# pulse_gen.net
KiCad netlist of a schematic drawn in Altium Designer
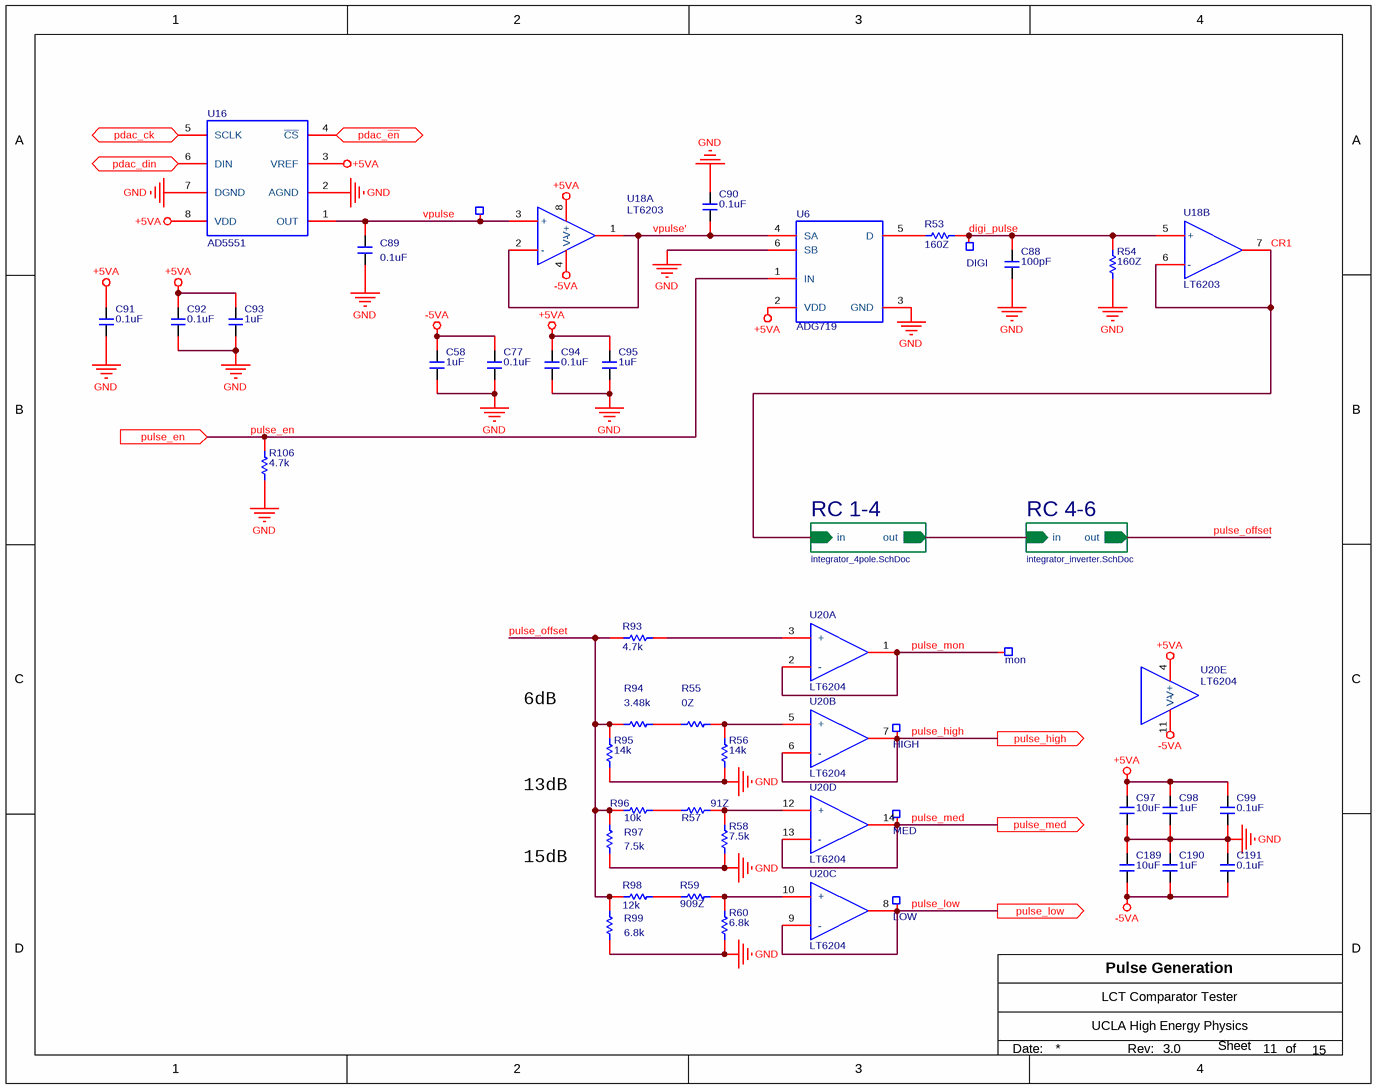
[diagram p0: pulse_gen.SchDoc]

(export (version "E")
  (design (tool "Eeschema 10.0.6"))
  (components
    (comp (ref "C58")
      (value "1uF")
      (footprint "C0603")
      (description "CAP-CER, 2, 1.0uF, 10%, 25V, 0603")
      (fields
        (field (name "MANUFACTURER") "Murata Electronics North America")
        (field (name "MANUFACTURER PART NUMBER") "GRM188R61E105KA12D")
      )
      (libsource (lib "stdlib") (part "Murata/GRM188R61E105KA12D"))
    )
    (comp (ref "C77")
      (value "0.1uF")
      (footprint "C0603")
      (description "CAP-CER, 2, 0.1uF, 10%, 50V, 0603, X7R")
      (fields
        (field (name "MANUFACTURER") "AVX Corporation")
        (field (name "MANUFACTURER PART NUMBER") "06035C104KAT2A")
      )
      (libsource (lib "stdlib") (part "CAP/06035C104KAT2A"))
    )
    (comp (ref "C88")
      (value "100pF")
      (footprint "C0603")
      (description "CAP-CER, 0, 100pF, 10%, 50V, 0603")
      (fields
        (field (name "MANUFACTURER") "AVX Corporation")
        (field (name "MANUFACTURER PART NUMBER") "06035A101KAT2A")
      )
      (libsource (lib "stdlib") (part "AVX/06035A101KAT2A"))
    )
    (comp (ref "C89")
      (value "0.1uF")
      (footprint "C0603")
      (description "CAP-CER, 2, 0.1uF, 10%, 50V, 0603, X7R")
      (fields
        (field (name "MANUFACTURER") "AVX Corporation")
        (field (name "MANUFACTURER PART NUMBER") "06035C104KAT2A")
      )
      (libsource (lib "stdlib") (part "CAP/06035C104KAT2A"))
    )
    (comp (ref "C90")
      (value "0.1uF")
      (footprint "C0603")
      (description "CAP-CER, 2, 0.1uF, 10%, 50V, 0603, X7R")
      (fields
        (field (name "MANUFACTURER") "AVX Corporation")
        (field (name "MANUFACTURER PART NUMBER") "06035C104KAT2A")
      )
      (libsource (lib "stdlib") (part "CAP/06035C104KAT2A"))
    )
    (comp (ref "C91")
      (value "0.1uF")
      (footprint "C0603")
      (description "CAP-CER, 2, 0.1uF, 10%, 50V, 0603, X7R")
      (fields
        (field (name "MANUFACTURER") "AVX Corporation")
        (field (name "MANUFACTURER PART NUMBER") "06035C104KAT2A")
      )
      (libsource (lib "stdlib") (part "CAP/06035C104KAT2A"))
    )
    (comp (ref "C92")
      (value "0.1uF")
      (footprint "C0603")
      (description "CAP-CER, 2, 0.1uF, 10%, 50V, 0603, X7R")
      (fields
        (field (name "MANUFACTURER") "AVX Corporation")
        (field (name "MANUFACTURER PART NUMBER") "06035C104KAT2A")
      )
      (libsource (lib "stdlib") (part "CAP/06035C104KAT2A"))
    )
    (comp (ref "C93")
      (value "1uF")
      (footprint "C0603")
      (description "CAP-CER, 2, 1.0uF, 10%, 25V, 0603")
      (fields
        (field (name "MANUFACTURER") "Murata Electronics North America")
        (field (name "MANUFACTURER PART NUMBER") "GRM188R61E105KA12D")
      )
      (libsource (lib "stdlib") (part "Murata/GRM188R61E105KA12D"))
    )
    (comp (ref "C94")
      (value "0.1uF")
      (footprint "C0603")
      (description "CAP-CER, 2, 0.1uF, 10%, 50V, 0603, X7R")
      (fields
        (field (name "MANUFACTURER") "AVX Corporation")
        (field (name "MANUFACTURER PART NUMBER") "06035C104KAT2A")
      )
      (libsource (lib "stdlib") (part "CAP/06035C104KAT2A"))
    )
    (comp (ref "C95")
      (value "1uF")
      (footprint "C0603")
      (description "CAP-CER, 2, 1.0uF, 10%, 25V, 0603")
      (fields
        (field (name "MANUFACTURER") "Murata Electronics North America")
        (field (name "MANUFACTURER PART NUMBER") "GRM188R61E105KA12D")
      )
      (libsource (lib "stdlib") (part "Murata/GRM188R61E105KA12D"))
    )
    (comp (ref "C97")
      (value "10uF")
      (footprint "c1206")
      (description "CAP-CER, 2, 10uF, 10%, 35V, 1206")
      (fields
        (field (name "MANUFACTURER") "Taiyo Yuden")
        (field (name "MANUFACTURER PART NUMBER") "GMK316F106ZL-T")
      )
      (libsource (lib "stdlib") (part "CAP/GMK316F106ZL-T"))
    )
    (comp (ref "C98")
      (value "1uF")
      (footprint "C0603")
      (description "CAP-CER, 2, 1.0uF, 10%, 25V, 0603")
      (fields
        (field (name "MANUFACTURER") "Murata Electronics North America")
        (field (name "MANUFACTURER PART NUMBER") "GRM188R61E105KA12D")
      )
      (libsource (lib "stdlib") (part "Murata/GRM188R61E105KA12D"))
    )
    (comp (ref "C99")
      (value "0.1uF")
      (footprint "C0603")
      (description "CAP-CER, 2, 0.1uF, 10%, 50V, 0603, X7R")
      (fields
        (field (name "MANUFACTURER") "AVX Corporation")
        (field (name "MANUFACTURER PART NUMBER") "06035C104KAT2A")
      )
      (libsource (lib "stdlib") (part "CAP/06035C104KAT2A"))
    )
    (comp (ref "C189")
      (value "10uF")
      (footprint "c1206")
      (description "CAP-CER, 2, 10uF, 10%, 35V, 1206")
      (fields
        (field (name "MANUFACTURER") "Taiyo Yuden")
        (field (name "MANUFACTURER PART NUMBER") "GMK316F106ZL-T")
      )
      (libsource (lib "stdlib") (part "CAP/GMK316F106ZL-T"))
    )
    (comp (ref "C190")
      (value "1uF")
      (footprint "C0603")
      (description "CAP-CER, 2, 1.0uF, 10%, 25V, 0603")
      (fields
        (field (name "MANUFACTURER") "Murata Electronics North America")
        (field (name "MANUFACTURER PART NUMBER") "GRM188R61E105KA12D")
      )
      (libsource (lib "stdlib") (part "Murata/GRM188R61E105KA12D"))
    )
    (comp (ref "C191")
      (value "0.1uF")
      (footprint "C0603")
      (description "CAP-CER, 2, 0.1uF, 10%, 50V, 0603, X7R")
      (fields
        (field (name "MANUFACTURER") "AVX Corporation")
        (field (name "MANUFACTURER PART NUMBER") "06035C104KAT2A")
      )
      (libsource (lib "stdlib") (part "CAP/06035C104KAT2A"))
    )
    (comp (ref "mon")
      (value "TP_SMALL")
      (footprint "TP_SMALL")
      (description "Test Point, Generic, 50MIL")
      (libsource (lib "stdlib") (part "TP_SMALL"))
    )
    (comp (ref "R53")
      (value "160Z")
      (footprint "R0603")
      (description "RES0, SMD,  160Z, 1.0%, 1/10W, 0603")
      (fields
        (field (name "MANUFACTURER") "Vishay Dale")
        (field (name "MANUFACTURER PART NUMBER") "CRCW0603160RFKEA")
      )
      (libsource (lib "stdlib") (part "CRCW0603160RFKEA"))
    )
    (comp (ref "R54")
      (value "160Z")
      (footprint "R0603")
      (description "RES0, SMD,  160Z, 1.0%, 1/10W, 0603")
      (fields
        (field (name "MANUFACTURER") "Vishay Dale")
        (field (name "MANUFACTURER PART NUMBER") "CRCW0603160RFKEA")
      )
      (libsource (lib "stdlib") (part "CRCW0603160RFKEA"))
    )
    (comp (ref "R55")
      (value "0Z")
      (footprint "R0805")
      (description "RES0, SMD, 0.00Z, 0805")
      (fields
        (field (name "MANUFACTURER") "Vishay Dale")
        (field (name "MANUFACTURER PART NUMBER") "CRCW08050000Z0EA")
      )
      (libsource (lib "stdlib") (part "CRCW08050000Z0EA"))
    )
    (comp (ref "R56")
      (value "14k")
      (footprint "R0805")
      (description "RES1, SMD, 14.0k, 1.0%, 1/8W, 0805")
      (fields
        (field (name "MANUFACTURER") "Yageo")
        (field (name "MANUFACTURER PART NUMBER") "RC0805FR-0714KL")
      )
      (libsource (lib "stdlib") (part "RC0805FR-0714KL"))
    )
    (comp (ref "R57")
      (value "91Z")
      (footprint "R0805")
      (description "RES0, SMD, 91Z, 1.0%, 1/8W, 0805")
      (fields
        (field (name "MANUFACTURER") "Panasonic Electronic Components")
        (field (name "MANUFACTURER PART NUMBER") "ERJ-6ENF91R0V")
      )
      (libsource (lib "stdlib") (part "ERJ-6ENF91R0V"))
    )
    (comp (ref "R58")
      (value "7.5k")
      (footprint "R0805")
      (description "RES1, SMD, 7.5k, 1.0%, 1/8W, 0805")
      (fields
        (field (name "MANUFACTURER") "Yageo")
        (field (name "MANUFACTURER PART NUMBER") "RC0805FR-077K5L")
      )
      (libsource (lib "stdlib") (part "RC0805FR-077K5L"))
    )
    (comp (ref "R59")
      (value "909Z")
      (footprint "R0805")
      (description "RES0, SMD, 6.8k, 1.0%, 1/8W, 0805")
      (fields
        (field (name "MANUFACTURER") "Yageo")
        (field (name "MANUFACTURER PART NUMBER") "RC0805FR-07909RL")
      )
      (libsource (lib "stdlib") (part "RC0805FR-07909RL"))
    )
    (comp (ref "R60")
      (value "6.8k")
      (footprint "R0805")
      (description "RES1, SMD, 6.8k, 1.0%, 1/8W, 0805")
      (fields
        (field (name "MANUFACTURER") "Yageo")
        (field (name "MANUFACTURER PART NUMBER") "RC0805FR-076K8L")
      )
      (libsource (lib "stdlib") (part "RC0805FR-076K8L"))
    )
    (comp (ref "R93")
      (value "4.7k")
      (footprint "R0805")
      (description "RES1, SMD, 4.70k, 1.0%, 1/10W, 0805")
      (fields
        (field (name "MANUFACTURER") "Vishay Dale")
        (field (name "MANUFACTURER PART NUMBER") "CRCW08054K70FKEA")
      )
      (libsource (lib "stdlib") (part "CRCW08054K70FKEA"))
    )
    (comp (ref "R94")
      (value "3.48k")
      (footprint "R0805")
      (description "RES1, SMD, 3.48k, 1.0%, 1/10W, 0805")
      (fields
        (field (name "MANUFACTURER") "Yageo")
        (field (name "MANUFACTURER PART NUMBER") "RC0805FR-073K48L")
      )
      (libsource (lib "stdlib") (part "RC0805FR-073K48L"))
    )
    (comp (ref "R95")
      (value "14k")
      (footprint "R0805")
      (description "RES1, SMD, 14.0k, 1.0%, 1/8W, 0805")
      (fields
        (field (name "MANUFACTURER") "Yageo")
        (field (name "MANUFACTURER PART NUMBER") "RC0805FR-0714KL")
      )
      (libsource (lib "stdlib") (part "RC0805FR-0714KL"))
    )
    (comp (ref "R96")
      (value "10k")
      (footprint "R0805")
      (description "RES1, SMD, 10.0k, 1.0%, 1/8W, 0805")
      (fields
        (field (name "MANUFACTURER") "Yageo")
        (field (name "MANUFACTURER PART NUMBER") "RC0805FR-0710KL")
      )
      (libsource (lib "stdlib") (part "RC0805FR-0710KL"))
    )
    (comp (ref "R97")
      (value "7.5k")
      (footprint "R0805")
      (description "RES1, SMD, 7.5k, 1.0%, 1/8W, 0805")
      (fields
        (field (name "MANUFACTURER") "Yageo")
        (field (name "MANUFACTURER PART NUMBER") "RC0805FR-077K5L")
      )
      (libsource (lib "stdlib") (part "RC0805FR-077K5L"))
    )
    (comp (ref "R98")
      (value "12k")
      (footprint "R0805")
      (description "RES1, SMD, 12.0k, 1.0%, 1/8W, 0805")
      (fields
        (field (name "MANUFACTURER") "Yageo")
        (field (name "MANUFACTURER PART NUMBER") "RC0805FR-0712KL")
      )
      (libsource (lib "stdlib") (part "RC0805FR-0712KL"))
    )
    (comp (ref "R99")
      (value "6.8k")
      (footprint "R0805")
      (description "RES1, SMD, 6.8k, 1.0%, 1/8W, 0805")
      (fields
        (field (name "MANUFACTURER") "Yageo")
        (field (name "MANUFACTURER PART NUMBER") "RC0805FR-076K8L")
      )
      (libsource (lib "stdlib") (part "RC0805FR-076K8L"))
    )
    (comp (ref "R106")
      (value "4.7k")
      (footprint "R0603")
      (description "RES1, SMD, 4.70k, 1.0%, 1/10W, 0603")
      (fields
        (field (name "MANUFACTURER") "Vishay Dale")
        (field (name "MANUFACTURER PART NUMBER") "CRCW06034K70FKEA")
      )
      (libsource (lib "stdlib") (part "CRCW06034K70FKEA"))
    )
    (comp (ref "TP27")
      (value "PDAC")
      (footprint "TP_MICRO")
      (description "Test Point, Round, Small")
      (libsource (lib "stdlib") (part "TP_MICRO"))
    )
    (comp (ref "TP28")
      (value "DIGI")
      (footprint "TP_MICRO")
      (description "Test Point, Round, Small")
      (libsource (lib "") (part "TP_MICRO_1"))
    )
    (comp (ref "TP29")
      (value "HIGH")
      (footprint "TP_MICRO")
      (description "Test Point, Round, Small")
      (libsource (lib "stdlib") (part "TP_MICRO"))
    )
    (comp (ref "TP30")
      (value "MED")
      (footprint "TP_MICRO")
      (description "Test Point, Round, Small")
      (libsource (lib "stdlib") (part "TP_MICRO"))
    )
    (comp (ref "TP31")
      (value "LOW")
      (footprint "TP_MICRO")
      (description "Test Point, Round, Small")
      (libsource (lib "stdlib") (part "TP_MICRO"))
    )
    (comp (ref "U6")
      (value "ADG719")
      (footprint "SOT23-6")
      (description "SWITCH, SPDT, 2:1, 4 Ohm")
      (fields
        (field (name "MANUFACTURER") "Analog Devices Inc.")
        (field (name "MANUFACTURER PART NUMBER") "ADG719BRTZ-500RL7")
      )
      (libsource (lib "stdlib") (part "ADG719 SOT23-6"))
    )
    (comp (ref "U16")
      (value "AD5551")
      (footprint "SOIC-8")
      (description "DAC, 14-BIT, 1MSPS")
      (fields
        (field (name "MANUFACTURER") "Analog Devices Inc.")
        (field (name "MANUFACTURER PART NUMBER") "AD5551BRZ")
      )
      (libsource (lib "stdlib") (part "AD/AD5551 SOIC-8"))
    )
    (comp (ref "U18")
      (value "LT6203")
      (footprint "SOIC-8")
      (description "OPA, 100MHz, Dual, RRIO, Single-supply, Unity Stable")
      (libsource (lib "stdlib") (part "LT6203 SOIC-8"))
    )
    (comp (ref "U20")
      (value "LT6204")
      (footprint "SOIC-14")
      (description "OPA, 100MHz, Quad, RRIO, Unity Stable")
      (libsource (lib "stdlib") (part "LT6204 SOIC-14"))
    )
  )
  (nets
    (net (code "1") (name "+5VA") (class "Default")
      (node (ref "C91") (pin "2") (pinfunction "2_2") (pintype "passive"))
      (node (ref "C92") (pin "2") (pinfunction "2_2") (pintype "passive"))
      (node (ref "C93") (pin "2") (pinfunction "2_2") (pintype "passive"))
      (node (ref "C94") (pin "2") (pinfunction "2_2") (pintype "passive"))
      (node (ref "C95") (pin "2") (pinfunction "2_2") (pintype "passive"))
      (node (ref "C97") (pin "1") (pinfunction "5_1") (pintype "passive"))
      (node (ref "C98") (pin "2") (pinfunction "2_2") (pintype "passive"))
      (node (ref "C99") (pin "2") (pinfunction "2_2") (pintype "passive"))
      (node (ref "U16") (pin "3") (pinfunction "VREF_3") (pintype "passive"))
      (node (ref "U16") (pin "8") (pinfunction "VDD_8") (pintype "passive"))
      (node (ref "U18") (pin "8") (pinfunction "V+_8") (pintype "passive"))
      (node (ref "U20") (pin "4") (pinfunction "V+_4") (pintype "passive"))
      (node (ref "U6") (pin "2") (pinfunction "VDD_2") (pintype "passive"))
    )
    (net (code "2") (name "-5VA") (class "Default")
      (node (ref "C189") (pin "2") (pinfunction "2_2") (pintype "passive"))
      (node (ref "C190") (pin "1") (pinfunction "5_1") (pintype "passive"))
      (node (ref "C191") (pin "1") (pinfunction "5_1") (pintype "passive"))
      (node (ref "C58") (pin "2") (pinfunction "2_2") (pintype "passive"))
      (node (ref "C77") (pin "2") (pinfunction "2_2") (pintype "passive"))
      (node (ref "U18") (pin "4") (pinfunction "V-_4") (pintype "passive"))
      (node (ref "U20") (pin "11") (pinfunction "V-_11") (pintype "passive"))
    )
    (net (code "3") (name "/CR1") (class "Default")
      (node (ref "U18") (pin "6") (pinfunction "-_6") (pintype "passive"))
      (node (ref "U18") (pin "7") (pinfunction "OUTB_7") (pintype "passive"))
    )
    (net (code "4") (name "/digi_pulse") (class "Default")
      (node (ref "C88") (pin "2") (pinfunction "2_2") (pintype "passive"))
      (node (ref "R53") (pin "2") (pinfunction "2_2") (pintype "passive"))
      (node (ref "R54") (pin "2") (pinfunction "2_2") (pintype "passive"))
      (node (ref "TP28") (pin "1") (pinfunction "1_1") (pintype "passive"))
      (node (ref "U18") (pin "5") (pinfunction "+_5") (pintype "passive"))
    )
    (net (code "6") (name "/pdac_ck") (class "Default")
      (node (ref "U16") (pin "5") (pinfunction "SCLK_5") (pintype "passive"))
    )
    (net (code "7") (name "/pdac_din") (class "Default")
      (node (ref "U16") (pin "6") (pinfunction "DIN_6") (pintype "passive"))
    )
    (net (code "8") (name "/pdac_~{en}") (class "Default")
      (node (ref "U16") (pin "4") (pinfunction "~{CS}_4") (pintype "passive"))
    )
    (net (code "9") (name "/pulse_en") (class "Default")
      (node (ref "R106") (pin "2") (pinfunction "2_2") (pintype "passive"))
      (node (ref "U6") (pin "1") (pinfunction "IN_1") (pintype "passive"))
    )
    (net (code "10") (name "/pulse_high") (class "Default")
      (node (ref "TP29") (pin "1") (pinfunction "1_1") (pintype "passive"))
      (node (ref "U20") (pin "6") (pinfunction "-_6") (pintype "passive"))
      (node (ref "U20") (pin "7") (pinfunction "OUT_7") (pintype "passive"))
    )
    (net (code "11") (name "/pulse_low") (class "Default")
      (node (ref "TP31") (pin "1") (pinfunction "1_1") (pintype "passive"))
      (node (ref "U20") (pin "8") (pinfunction "OUT_8") (pintype "passive"))
      (node (ref "U20") (pin "9") (pinfunction "-_9") (pintype "passive"))
    )
    (net (code "12") (name "/pulse_med") (class "Default")
      (node (ref "TP30") (pin "1") (pinfunction "1_1") (pintype "passive"))
      (node (ref "U20") (pin "13") (pinfunction "-_13") (pintype "passive"))
      (node (ref "U20") (pin "14") (pinfunction "OUT_14") (pintype "passive"))
    )
    (net (code "13") (name "/pulse_mon") (class "Default")
      (node (ref "U20") (pin "1") (pinfunction "OUT_1") (pintype "passive"))
      (node (ref "U20") (pin "2") (pinfunction "-_2") (pintype "passive"))
      (node (ref "mon") (pin "1") (pinfunction "1_1") (pintype "passive"))
    )
    (net (code "14") (name "/pulse_offset") (class "Default")
      (node (ref "R93") (pin "1") (pinfunction "1_1") (pintype "passive"))
      (node (ref "R94") (pin "1") (pinfunction "1_1") (pintype "passive"))
      (node (ref "R95") (pin "2") (pinfunction "2_2") (pintype "passive"))
      (node (ref "R96") (pin "1") (pinfunction "1_1") (pintype "passive"))
      (node (ref "R97") (pin "2") (pinfunction "2_2") (pintype "passive"))
      (node (ref "R98") (pin "1") (pinfunction "1_1") (pintype "passive"))
      (node (ref "R99") (pin "2") (pinfunction "2_2") (pintype "passive"))
    )
    (net (code "15") (name "/vpulse") (class "Default")
      (node (ref "C89") (pin "2") (pinfunction "2_2") (pintype "passive"))
      (node (ref "TP27") (pin "1") (pinfunction "1_1") (pintype "passive"))
      (node (ref "U16") (pin "1") (pinfunction "OUT_1") (pintype "passive"))
      (node (ref "U18") (pin "3") (pinfunction "+_3") (pintype "passive"))
    )
    (net (code "16") (name "/vpulse'") (class "Default")
      (node (ref "C90") (pin "2") (pinfunction "2_2") (pintype "passive"))
      (node (ref "U18") (pin "1") (pinfunction "OUTA_1") (pintype "passive"))
      (node (ref "U18") (pin "2") (pinfunction "-_2") (pintype "passive"))
      (node (ref "U6") (pin "4") (pinfunction "SA_4") (pintype "passive"))
    )
    (net (code "17") (name "GND") (class "Default")
      (node (ref "C189") (pin "1") (pinfunction "5_1") (pintype "passive"))
      (node (ref "C190") (pin "2") (pinfunction "2_2") (pintype "passive"))
      (node (ref "C191") (pin "2") (pinfunction "2_2") (pintype "passive"))
      (node (ref "C58") (pin "1") (pinfunction "5_1") (pintype "passive"))
      (node (ref "C77") (pin "1") (pinfunction "5_1") (pintype "passive"))
      (node (ref "C88") (pin "1") (pinfunction "5_1") (pintype "passive"))
      (node (ref "C89") (pin "1") (pinfunction "5_1") (pintype "passive"))
      (node (ref "C90") (pin "1") (pinfunction "5_1") (pintype "passive"))
      (node (ref "C91") (pin "1") (pinfunction "5_1") (pintype "passive"))
      (node (ref "C92") (pin "1") (pinfunction "5_1") (pintype "passive"))
      (node (ref "C93") (pin "1") (pinfunction "5_1") (pintype "passive"))
      (node (ref "C94") (pin "1") (pinfunction "5_1") (pintype "passive"))
      (node (ref "C95") (pin "1") (pinfunction "5_1") (pintype "passive"))
      (node (ref "C97") (pin "2") (pinfunction "2_2") (pintype "passive"))
      (node (ref "C98") (pin "1") (pinfunction "5_1") (pintype "passive"))
      (node (ref "C99") (pin "1") (pinfunction "5_1") (pintype "passive"))
      (node (ref "R106") (pin "1") (pinfunction "1_1") (pintype "passive"))
      (node (ref "R54") (pin "1") (pinfunction "1_1") (pintype "passive"))
      (node (ref "R56") (pin "1") (pinfunction "1_1") (pintype "passive"))
      (node (ref "R58") (pin "1") (pinfunction "1_1") (pintype "passive"))
      (node (ref "R60") (pin "1") (pinfunction "1_1") (pintype "passive"))
      (node (ref "R95") (pin "1") (pinfunction "1_1") (pintype "passive"))
      (node (ref "R97") (pin "1") (pinfunction "1_1") (pintype "passive"))
      (node (ref "R99") (pin "1") (pinfunction "1_1") (pintype "passive"))
      (node (ref "U16") (pin "2") (pinfunction "AGND_2") (pintype "passive"))
      (node (ref "U16") (pin "7") (pinfunction "DGND_7") (pintype "passive"))
      (node (ref "U6") (pin "3") (pinfunction "GND_3") (pintype "passive"))
      (node (ref "U6") (pin "6") (pinfunction "SB_6") (pintype "passive"))
    )
    (net (code "18") (name "Net-(R55-Pad1)") (class "Default")
      (node (ref "R55") (pin "1") (pinfunction "1_1") (pintype "passive"))
      (node (ref "R94") (pin "2") (pinfunction "2_2") (pintype "passive"))
    )
    (net (code "19") (name "Net-(R57-Pad1)") (class "Default")
      (node (ref "R57") (pin "1") (pinfunction "1_1") (pintype "passive"))
      (node (ref "R96") (pin "2") (pinfunction "2_2") (pintype "passive"))
    )
    (net (code "20") (name "Net-(R59-Pad2)") (class "Default")
      (node (ref "R59") (pin "2") (pinfunction "2_2") (pintype "passive"))
      (node (ref "R98") (pin "2") (pinfunction "2_2") (pintype "passive"))
    )
    (net (code "21") (name "Net-(U6-D)") (class "Default")
      (node (ref "R53") (pin "1") (pinfunction "1_1") (pintype "passive"))
      (node (ref "U6") (pin "5") (pinfunction "D_5") (pintype "passive"))
    )
    (net (code "22") (name "Net-(U20A-+)") (class "Default")
      (node (ref "R93") (pin "2") (pinfunction "2_2") (pintype "passive"))
      (node (ref "U20") (pin "3") (pinfunction "+_3") (pintype "passive"))
    )
    (net (code "23") (name "Net-(U20B-+)") (class "Default")
      (node (ref "R55") (pin "2") (pinfunction "2_2") (pintype "passive"))
      (node (ref "R56") (pin "2") (pinfunction "2_2") (pintype "passive"))
      (node (ref "U20") (pin "5") (pinfunction "+_5") (pintype "passive"))
    )
    (net (code "24") (name "Net-(U20C-+)") (class "Default")
      (node (ref "R59") (pin "1") (pinfunction "1_1") (pintype "passive"))
      (node (ref "R60") (pin "2") (pinfunction "2_2") (pintype "passive"))
      (node (ref "U20") (pin "10") (pinfunction "+_10") (pintype "passive"))
    )
    (net (code "25") (name "Net-(U20D-+)") (class "Default")
      (node (ref "R57") (pin "2") (pinfunction "2_2") (pintype "passive"))
      (node (ref "R58") (pin "2") (pinfunction "2_2") (pintype "passive"))
      (node (ref "U20") (pin "12") (pinfunction "+_12") (pintype "passive"))
    )
    (net (code "26") (name "unconnected-(U6-NC-Pad5)") (class "Default")
      (node (ref "U6") (pin "5") (pinfunction "NC_5") (pintype "passive"))
    )
  )
)
